# tx.net
KiCad netlist of a schematic drawn in EAGLE
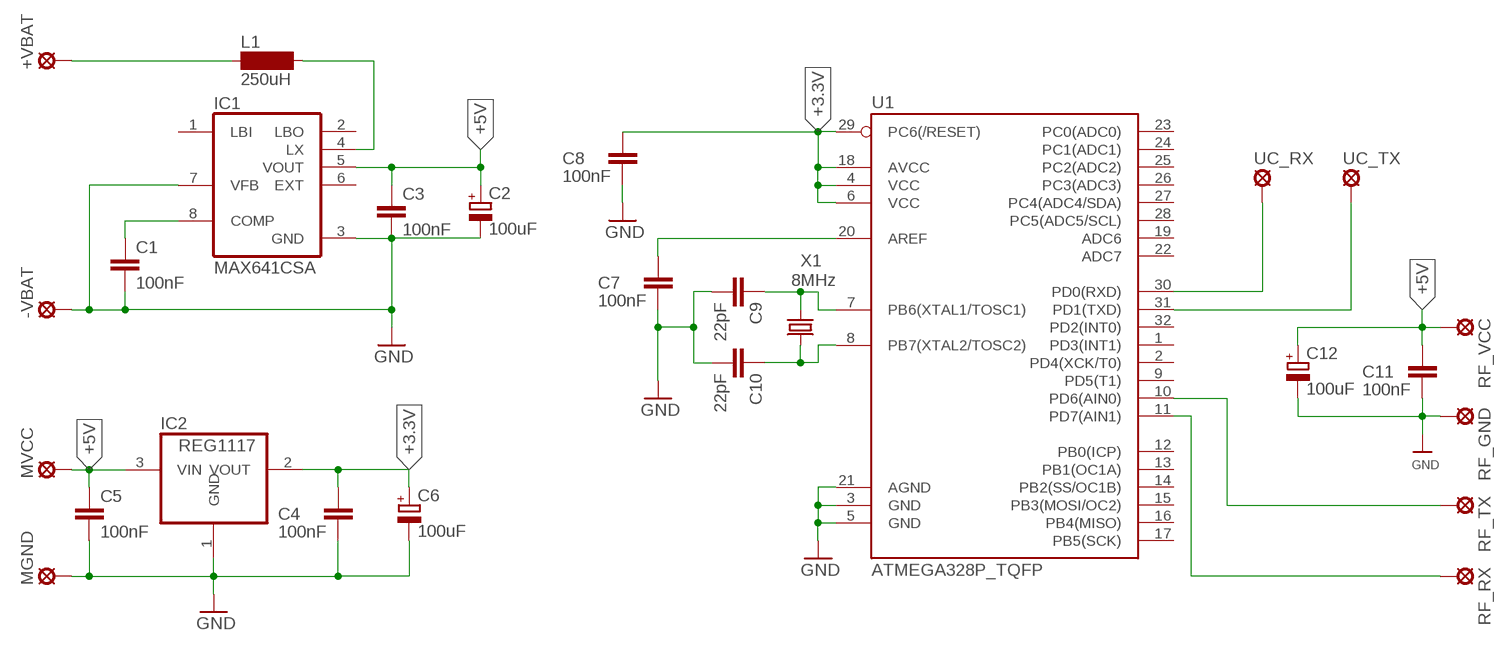
[diagram p0: schematic, sheet 1]

(export (version "E")
  (design (tool "Eeschema 10.0.6"))
  (components
    (comp (ref "+VBAT")
      (value "SE14")
      (footprint "eagle-import:SE14")
      (libsource (lib "eagle-import") (part "SE14"))
    )
    (comp (ref "-VBAT")
      (value "SE14")
      (footprint "eagle-import:SE14")
      (libsource (lib "eagle-import") (part "SE14"))
    )
    (comp (ref "C1")
      (value "100nF")
      (footprint "eagle-import:C1206")
      (libsource (lib "eagle-import") (part "C-EUC1206"))
    )
    (comp (ref "C2")
      (value "100uF")
      (footprint "eagle-import:140CLH-0810")
      (libsource (lib "eagle-import") (part "CPOL-EU140CLH-0810"))
    )
    (comp (ref "C3")
      (value "100nF")
      (footprint "eagle-import:C1206")
      (libsource (lib "eagle-import") (part "C-EUC1206"))
    )
    (comp (ref "C4")
      (value "100nF")
      (footprint "eagle-import:C1206")
      (libsource (lib "eagle-import") (part "C-EUC1206"))
    )
    (comp (ref "C5")
      (value "100nF")
      (footprint "eagle-import:C1206")
      (libsource (lib "eagle-import") (part "C-EUC1206"))
    )
    (comp (ref "C6")
      (value "100uF")
      (footprint "eagle-import:140CLH-0810")
      (libsource (lib "eagle-import") (part "CPOL-EU140CLH-0810"))
    )
    (comp (ref "C7")
      (value "100nF")
      (footprint "eagle-import:C1206")
      (libsource (lib "eagle-import") (part "C-EUC1206"))
    )
    (comp (ref "C8")
      (value "100nF")
      (footprint "eagle-import:C1206")
      (libsource (lib "eagle-import") (part "C-EUC1206"))
    )
    (comp (ref "C9")
      (value "22pF")
      (footprint "eagle-import:0603")
      (libsource (lib "eagle-import") (part "22PF-0603-50V-5%"))
    )
    (comp (ref "C10")
      (value "22pF")
      (footprint "eagle-import:0603")
      (libsource (lib "eagle-import") (part "22PF-0603-50V-5%"))
    )
    (comp (ref "C11")
      (value "100nF")
      (footprint "eagle-import:C1206")
      (libsource (lib "eagle-import") (part "C-EUC1206"))
    )
    (comp (ref "C12")
      (value "100uF")
      (footprint "eagle-import:140CLH-0810")
      (libsource (lib "eagle-import") (part "CPOL-EU140CLH-0810"))
    )
    (comp (ref "IC1")
      (value "MAX641CSA")
      (footprint "eagle-import:SO08")
      (libsource (lib "eagle-import") (part "MAX641CSA"))
    )
    (comp (ref "IC2")
      (value "REG1117")
      (footprint "eagle-import:SOT223")
      (libsource (lib "eagle-import") (part "REG1117"))
    )
    (comp (ref "L1")
      (value "250uH")
      (footprint "eagle-import:MS50")
      (libsource (lib "eagle-import") (part "MS50"))
    )
    (comp (ref "MGND")
      (value "SE14")
      (footprint "eagle-import:SE14")
      (libsource (lib "eagle-import") (part "SE14"))
    )
    (comp (ref "MVCC")
      (value "SE14")
      (footprint "eagle-import:SE14")
      (libsource (lib "eagle-import") (part "SE14"))
    )
    (comp (ref "RF_GND")
      (value "SE14")
      (footprint "eagle-import:SE14")
      (libsource (lib "eagle-import") (part "SE14"))
    )
    (comp (ref "RF_RX")
      (value "SE14")
      (footprint "eagle-import:SE14")
      (libsource (lib "eagle-import") (part "SE14"))
    )
    (comp (ref "RF_TX")
      (value "SE14")
      (footprint "eagle-import:SE14")
      (libsource (lib "eagle-import") (part "SE14"))
    )
    (comp (ref "RF_VCC")
      (value "SE14")
      (footprint "eagle-import:SE14")
      (libsource (lib "eagle-import") (part "SE14"))
    )
    (comp (ref "U1")
      (value "ATMEGA328P_TQFP")
      (footprint "eagle-import:TQFP32-08")
      (libsource (lib "eagle-import") (part "ATMEGA328P_TQFP"))
    )
    (comp (ref "UC_RX")
      (value "SE14")
      (footprint "eagle-import:SE14")
      (libsource (lib "eagle-import") (part "SE14"))
    )
    (comp (ref "UC_TX")
      (value "SE14")
      (footprint "eagle-import:SE14")
      (libsource (lib "eagle-import") (part "SE14"))
    )
    (comp (ref "X1")
      (value "8MHz")
      (footprint "eagle-import:CSM-7X-DU")
      (libsource (lib "eagle-import") (part "CSM-7X-DU"))
    )
  )
  (nets
    (net (code "1") (name "+3.3V") (class "Default")
      (node (ref "C4") (pin "1") (pinfunction "1_1") (pintype "passive"))
      (node (ref "C6") (pin "+") (pinfunction "+_+") (pintype "passive"))
      (node (ref "C8") (pin "1") (pinfunction "1_1") (pintype "passive"))
      (node (ref "IC2") (pin "2") (pinfunction "VOUT_2") (pintype "output"))
      (node (ref "U1") (pin "18") (pinfunction "AVCC_18") (pintype "bidirectional"))
      (node (ref "U1") (pin "29") (pinfunction "PC6(/RESET)_29") (pintype "bidirectional"))
      (node (ref "U1") (pin "4") (pinfunction "VCC_4") (pintype "bidirectional"))
      (node (ref "U1") (pin "6") (pinfunction "VCC_6") (pintype "bidirectional"))
    )
    (net (code "2") (name "+5V") (class "Default")
      (node (ref "C11") (pin "1") (pinfunction "1_1") (pintype "passive"))
      (node (ref "C12") (pin "+") (pinfunction "+_+") (pintype "passive"))
      (node (ref "C2") (pin "+") (pinfunction "+_+") (pintype "passive"))
      (node (ref "C3") (pin "1") (pinfunction "1_1") (pintype "passive"))
      (node (ref "C5") (pin "1") (pinfunction "1_1") (pintype "passive"))
      (node (ref "IC1") (pin "5") (pinfunction "VOUT_5") (pintype "output"))
      (node (ref "IC2") (pin "3") (pinfunction "VIN_3") (pintype "input"))
      (node (ref "MVCC") (pin "MP") (pinfunction "MP_MP") (pintype "passive"))
      (node (ref "RF_VCC") (pin "MP") (pinfunction "MP_MP") (pintype "passive"))
    )
    (net (code "3") (name "GND") (class "Default")
      (node (ref "-VBAT") (pin "MP") (pinfunction "MP_MP") (pintype "passive"))
      (node (ref "C1") (pin "2") (pinfunction "2_2") (pintype "passive"))
      (node (ref "C10") (pin "2") (pinfunction "2_2") (pintype "passive"))
      (node (ref "C11") (pin "2") (pinfunction "2_2") (pintype "passive"))
      (node (ref "C12") (pin "-") (pinfunction "-_-") (pintype "passive"))
      (node (ref "C2") (pin "-") (pinfunction "-_-") (pintype "passive"))
      (node (ref "C3") (pin "2") (pinfunction "2_2") (pintype "passive"))
      (node (ref "C4") (pin "2") (pinfunction "2_2") (pintype "passive"))
      (node (ref "C5") (pin "2") (pinfunction "2_2") (pintype "passive"))
      (node (ref "C6") (pin "-") (pinfunction "-_-") (pintype "passive"))
      (node (ref "C7") (pin "2") (pinfunction "2_2") (pintype "passive"))
      (node (ref "C8") (pin "2") (pinfunction "2_2") (pintype "passive"))
      (node (ref "C9") (pin "2") (pinfunction "2_2") (pintype "passive"))
      (node (ref "IC1") (pin "3") (pinfunction "GND_3") (pintype "power_in"))
      (node (ref "IC1") (pin "7") (pinfunction "VFB_7") (pintype "input"))
      (node (ref "IC2") (pin "1") (pinfunction "GND_1") (pintype "power_in"))
      (node (ref "MGND") (pin "MP") (pinfunction "MP_MP") (pintype "passive"))
      (node (ref "RF_GND") (pin "MP") (pinfunction "MP_MP") (pintype "passive"))
      (node (ref "U1") (pin "21") (pinfunction "AGND_21") (pintype "bidirectional"))
      (node (ref "U1") (pin "3") (pinfunction "GND_3") (pintype "bidirectional"))
      (node (ref "U1") (pin "5") (pinfunction "GND_5") (pintype "bidirectional"))
    )
    (net (code "4") (name "Net-(+VBAT-PadMP)") (class "Default")
      (node (ref "+VBAT") (pin "MP") (pinfunction "MP_MP") (pintype "passive"))
      (node (ref "L1") (pin "1") (pinfunction "1_1") (pintype "passive"))
    )
    (net (code "5") (name "Net-(IC1-COMP)") (class "Default")
      (node (ref "C1") (pin "1") (pinfunction "1_1") (pintype "passive"))
      (node (ref "IC1") (pin "8") (pinfunction "COMP_8") (pintype "input"))
    )
    (net (code "6") (name "Net-(IC1-LX)") (class "Default")
      (node (ref "IC1") (pin "4") (pinfunction "LX_4") (pintype "output"))
      (node (ref "L1") (pin "2") (pinfunction "2_2") (pintype "passive"))
    )
    (net (code "7") (name "Net-(U1-AREF)") (class "Default")
      (node (ref "C7") (pin "1") (pinfunction "1_1") (pintype "passive"))
      (node (ref "U1") (pin "20") (pinfunction "AREF_20") (pintype "bidirectional"))
    )
    (net (code "8") (name "Net-(U1-PB6(XTAL1{slash}TOSC1))") (class "Default")
      (node (ref "C9") (pin "1") (pinfunction "1_1") (pintype "passive"))
      (node (ref "U1") (pin "7") (pinfunction "PB6(XTAL1/TOSC1)_7") (pintype "bidirectional"))
      (node (ref "X1") (pin "1") (pinfunction "1_1") (pintype "passive"))
    )
    (net (code "9") (name "Net-(U1-PB7(XTAL2{slash}TOSC2))") (class "Default")
      (node (ref "C10") (pin "1") (pinfunction "1_1") (pintype "passive"))
      (node (ref "U1") (pin "8") (pinfunction "PB7(XTAL2/TOSC2)_8") (pintype "bidirectional"))
      (node (ref "X1") (pin "2") (pinfunction "2_2") (pintype "passive"))
    )
    (net (code "10") (name "Net-(U1-PD0(RXD))") (class "Default")
      (node (ref "U1") (pin "30") (pinfunction "PD0(RXD)_30") (pintype "bidirectional"))
      (node (ref "UC_RX") (pin "MP") (pinfunction "MP_MP") (pintype "passive"))
    )
    (net (code "11") (name "Net-(U1-PD1(TXD))") (class "Default")
      (node (ref "U1") (pin "31") (pinfunction "PD1(TXD)_31") (pintype "bidirectional"))
      (node (ref "UC_TX") (pin "MP") (pinfunction "MP_MP") (pintype "passive"))
    )
    (net (code "12") (name "Net-(U1-PD6(AIN0))") (class "Default")
      (node (ref "RF_TX") (pin "MP") (pinfunction "MP_MP") (pintype "passive"))
      (node (ref "U1") (pin "10") (pinfunction "PD6(AIN0)_10") (pintype "bidirectional"))
    )
    (net (code "13") (name "Net-(U1-PD7(AIN1))") (class "Default")
      (node (ref "RF_RX") (pin "MP") (pinfunction "MP_MP") (pintype "passive"))
      (node (ref "U1") (pin "11") (pinfunction "PD7(AIN1)_11") (pintype "bidirectional"))
    )
    (net (code "14") (name "unconnected-(IC1-EXT-Pad6)") (class "Default")
      (node (ref "IC1") (pin "6") (pinfunction "EXT_6") (pintype "output"))
    )
    (net (code "15") (name "unconnected-(IC1-LBI-Pad1)") (class "Default")
      (node (ref "IC1") (pin "1") (pinfunction "LBI_1") (pintype "input"))
    )
    (net (code "16") (name "unconnected-(IC1-LBO-Pad2)") (class "Default")
      (node (ref "IC1") (pin "2") (pinfunction "LBO_2") (pintype "output"))
    )
    (net (code "17") (name "unconnected-(U1-ADC6-Pad19)") (class "Default")
      (node (ref "U1") (pin "19") (pinfunction "ADC6_19") (pintype "bidirectional"))
    )
    (net (code "18") (name "unconnected-(U1-ADC7-Pad22)") (class "Default")
      (node (ref "U1") (pin "22") (pinfunction "ADC7_22") (pintype "bidirectional"))
    )
    (net (code "19") (name "unconnected-(U1-PB0(ICP)-Pad12)") (class "Default")
      (node (ref "U1") (pin "12") (pinfunction "PB0(ICP)_12") (pintype "bidirectional"))
    )
    (net (code "20") (name "unconnected-(U1-PB1(OC1A)-Pad13)") (class "Default")
      (node (ref "U1") (pin "13") (pinfunction "PB1(OC1A)_13") (pintype "bidirectional"))
    )
    (net (code "21") (name "unconnected-(U1-PB2(SS{slash}OC1B)-Pad14)") (class "Default")
      (node (ref "U1") (pin "14") (pinfunction "PB2(SS/OC1B)_14") (pintype "bidirectional"))
    )
    (net (code "22") (name "unconnected-(U1-PB3(MOSI{slash}OC2)-Pad15)") (class "Default")
      (node (ref "U1") (pin "15") (pinfunction "PB3(MOSI/OC2)_15") (pintype "bidirectional"))
    )
    (net (code "23") (name "unconnected-(U1-PB4(MISO)-Pad16)") (class "Default")
      (node (ref "U1") (pin "16") (pinfunction "PB4(MISO)_16") (pintype "bidirectional"))
    )
    (net (code "24") (name "unconnected-(U1-PB5(SCK)-Pad17)") (class "Default")
      (node (ref "U1") (pin "17") (pinfunction "PB5(SCK)_17") (pintype "bidirectional"))
    )
    (net (code "25") (name "unconnected-(U1-PC0(ADC0)-Pad23)") (class "Default")
      (node (ref "U1") (pin "23") (pinfunction "PC0(ADC0)_23") (pintype "bidirectional"))
    )
    (net (code "26") (name "unconnected-(U1-PC1(ADC1)-Pad24)") (class "Default")
      (node (ref "U1") (pin "24") (pinfunction "PC1(ADC1)_24") (pintype "bidirectional"))
    )
    (net (code "27") (name "unconnected-(U1-PC2(ADC2)-Pad25)") (class "Default")
      (node (ref "U1") (pin "25") (pinfunction "PC2(ADC2)_25") (pintype "bidirectional"))
    )
    (net (code "28") (name "unconnected-(U1-PC3(ADC3)-Pad26)") (class "Default")
      (node (ref "U1") (pin "26") (pinfunction "PC3(ADC3)_26") (pintype "bidirectional"))
    )
    (net (code "29") (name "unconnected-(U1-PC4(ADC4{slash}SDA)-Pad27)") (class "Default")
      (node (ref "U1") (pin "27") (pinfunction "PC4(ADC4/SDA)_27") (pintype "bidirectional"))
    )
    (net (code "30") (name "unconnected-(U1-PC5(ADC5{slash}SCL)-Pad28)") (class "Default")
      (node (ref "U1") (pin "28") (pinfunction "PC5(ADC5/SCL)_28") (pintype "bidirectional"))
    )
    (net (code "31") (name "unconnected-(U1-PD2(INT0)-Pad32)") (class "Default")
      (node (ref "U1") (pin "32") (pinfunction "PD2(INT0)_32") (pintype "bidirectional"))
    )
    (net (code "32") (name "unconnected-(U1-PD3(INT1)-Pad1)") (class "Default")
      (node (ref "U1") (pin "1") (pinfunction "PD3(INT1)_1") (pintype "bidirectional"))
    )
    (net (code "33") (name "unconnected-(U1-PD4(XCK{slash}T0)-Pad2)") (class "Default")
      (node (ref "U1") (pin "2") (pinfunction "PD4(XCK/T0)_2") (pintype "bidirectional"))
    )
    (net (code "34") (name "unconnected-(U1-PD5(T1)-Pad9)") (class "Default")
      (node (ref "U1") (pin "9") (pinfunction "PD5(T1)_9") (pintype "bidirectional"))
    )
  )
)
